# LedBlinker.net
KiCad netlist of a schematic drawn in Altium Designer
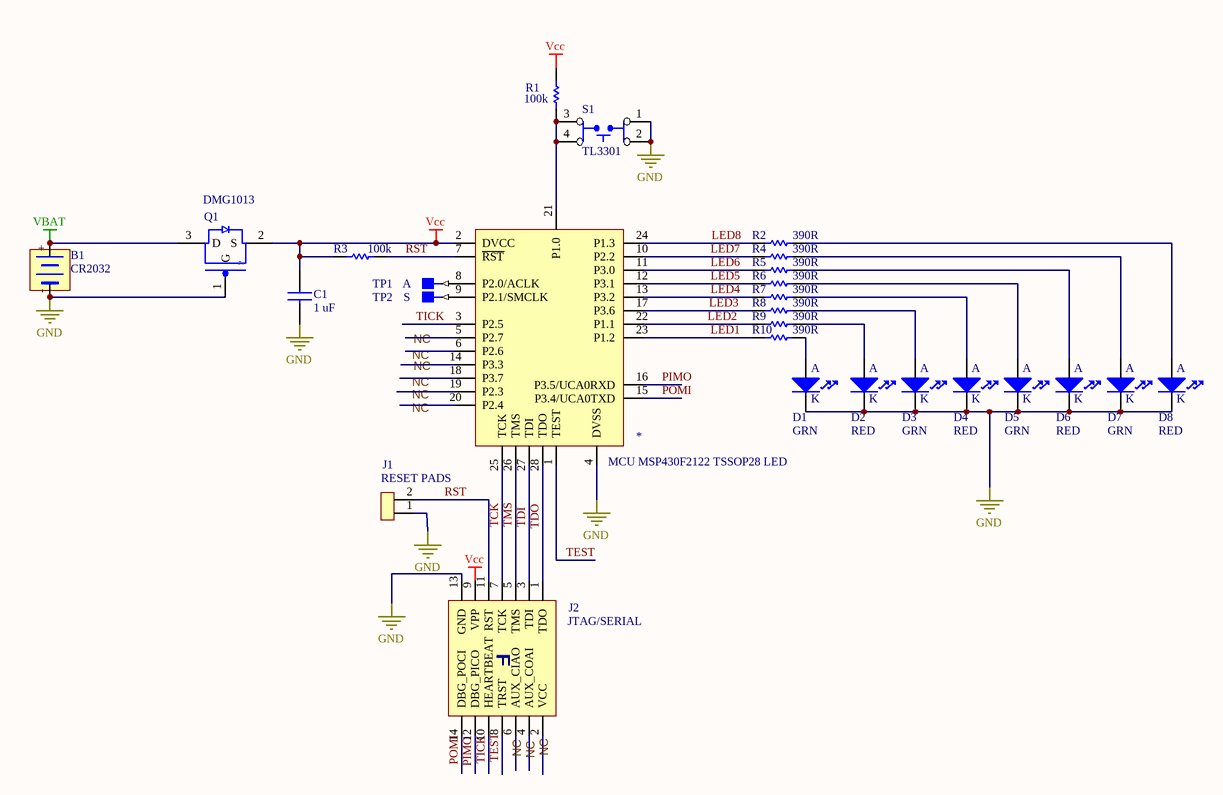
[diagram p0: LedBlinker.SchDoc]

(export (version "E")
  (design (tool "Eeschema 10.0.6"))
  (components
    (comp (ref "*")
      (value "MCU MSP430F2122 TSSOP28 LED")
      (fields (field (name "7. MODIFIED BY") "*"))
      (libsource (lib "Altium Example Master Schematic Library") (part "MCU MSP430F2122 TSSOP28 LED"))
    )
    (comp (ref "B1")
      (value "CR2032")
      (footprint "CONN BATTERY HOLDER CR2032")
      (description "3V Coincell Battery")
      (fields
        (field (name "3. MANUFACTURER PART NUMBER") "BK-912")
        (field (name "4. DIGI-KEY PART NUMBER") "BK-912-ND")
        (field (name "7. MODIFIED BY") "JRL")
      )
      (libsource (lib "Altium Example Master Schematic Library") (part "CONN BATTERY HOLDER CR2032"))
    )
    (comp (ref "C1")
      (value "1 uF")
      (footprint "0603")
      (fields (field (name "7. MODIFIED BY") "*"))
      (libsource (lib "Altium Example Master Schematic Library") (part "CAPACITOR NON-POLARIZED"))
    )
    (comp (ref "D1")
      (value "GRN")
      (footprint "PLCC-2 AK")
      (fields (field (name "7. MODIFIED BY") "*"))
      (libsource (lib "Altium Example Master Schematic Library") (part "LED AK"))
    )
    (comp (ref "D2")
      (value "RED")
      (footprint "PLCC-2 AK")
      (fields (field (name "7. MODIFIED BY") "*"))
      (libsource (lib "Altium Example Master Schematic Library") (part "LED AK"))
    )
    (comp (ref "D3")
      (value "GRN")
      (footprint "PLCC-2 AK")
      (fields (field (name "7. MODIFIED BY") "*"))
      (libsource (lib "Altium Example Master Schematic Library") (part "LED AK"))
    )
    (comp (ref "D4")
      (value "RED")
      (footprint "PLCC-2 AK")
      (fields (field (name "7. MODIFIED BY") "*"))
      (libsource (lib "Altium Example Master Schematic Library") (part "LED AK"))
    )
    (comp (ref "D5")
      (value "GRN")
      (footprint "PLCC-2 AK")
      (fields (field (name "7. MODIFIED BY") "*"))
      (libsource (lib "Altium Example Master Schematic Library") (part "LED AK"))
    )
    (comp (ref "D6")
      (value "RED")
      (footprint "PLCC-2 AK")
      (fields (field (name "7. MODIFIED BY") "*"))
      (libsource (lib "Altium Example Master Schematic Library") (part "LED AK"))
    )
    (comp (ref "D7")
      (value "GRN")
      (footprint "PLCC-2 AK")
      (fields (field (name "7. MODIFIED BY") "*"))
      (libsource (lib "Altium Example Master Schematic Library") (part "LED AK"))
    )
    (comp (ref "D8")
      (value "RED")
      (footprint "PLCC-2 AK")
      (fields (field (name "7. MODIFIED BY") "*"))
      (libsource (lib "Altium Example Master Schematic Library") (part "LED AK"))
    )
    (comp (ref "J1")
      (value "RESET PADS")
      (footprint "HDR1X2")
      (fields (field (name "7. MODIFIED BY") "*"))
      (libsource (lib "Altium Example Master Schematic Library") (part "CONN SIP 2"))
    )
    (comp (ref "J2")
      (value "JTAG/SERIAL")
      (footprint "CONN 14POS 7X2 SMT FEMALE SMALL")
      (fields
        (field (name "3. MANUFACTURER PART NUMBER") "20021321-00014T4LF")
        (field (name "4. DIGI-KEY PART NUMBER") "609-3771-ND")
        (field (name "5. INTERNAL PART NUMBER") "100254")
        (field (name "7. MODIFIED BY") "AAL")
      )
      (libsource (lib "Altium Example Master Schematic Library") (part "CONN JTAG/SERIAL FEMALE"))
    )
    (comp (ref "Q1")
      (value "DMG1013")
      (footprint "SC-70-3")
      (fields (field (name "7. MODIFIED BY") "*"))
      (libsource (lib "Altium Example Master Schematic Library") (part "TRANS PMOS 1G 2S 3D"))
    )
    (comp (ref "R1")
      (value "100k")
      (footprint "0603")
      (fields (field (name "7. MODIFIED BY") "*"))
      (libsource (lib "Altium Example Master Schematic Library") (part "RESISTOR"))
    )
    (comp (ref "R2")
      (value "390R")
      (footprint "0603")
      (fields (field (name "7. MODIFIED BY") "*"))
      (libsource (lib "Altium Example Master Schematic Library") (part "RESISTOR"))
    )
    (comp (ref "R3")
      (value "100k")
      (footprint "0603")
      (fields (field (name "7. MODIFIED BY") "*"))
      (libsource (lib "Altium Example Master Schematic Library") (part "RESISTOR"))
    )
    (comp (ref "R4")
      (value "390R")
      (footprint "0603")
      (fields (field (name "7. MODIFIED BY") "*"))
      (libsource (lib "Altium Example Master Schematic Library") (part "RESISTOR"))
    )
    (comp (ref "R5")
      (value "390R")
      (footprint "0603")
      (fields (field (name "7. MODIFIED BY") "*"))
      (libsource (lib "Altium Example Master Schematic Library") (part "RESISTOR"))
    )
    (comp (ref "R6")
      (value "390R")
      (footprint "0603")
      (fields (field (name "7. MODIFIED BY") "*"))
      (libsource (lib "Altium Example Master Schematic Library") (part "RESISTOR"))
    )
    (comp (ref "R7")
      (value "390R")
      (footprint "0603")
      (fields (field (name "7. MODIFIED BY") "*"))
      (libsource (lib "Altium Example Master Schematic Library") (part "RESISTOR"))
    )
    (comp (ref "R8")
      (value "390R")
      (footprint "0603")
      (fields (field (name "7. MODIFIED BY") "*"))
      (libsource (lib "Altium Example Master Schematic Library") (part "RESISTOR"))
    )
    (comp (ref "R9")
      (value "390R")
      (footprint "0603")
      (fields (field (name "7. MODIFIED BY") "*"))
      (libsource (lib "Altium Example Master Schematic Library") (part "RESISTOR"))
    )
    (comp (ref "R10")
      (value "390R")
      (footprint "0603")
      (fields (field (name "7. MODIFIED BY") "*"))
      (libsource (lib "Altium Example Master Schematic Library") (part "RESISTOR"))
    )
    (comp (ref "S1")
      (value "TL3301")
      (footprint "SWITCH TACT SMT TL3301 J LEAD")
      (description "SPST TACT SWITCH")
      (fields (field (name "3. MANUFACTURER PART NUMBER") "TL3301xxx") (field (name "7. MODIFIED BY") "JRL"))
      (libsource (lib "Altium Example Master Schematic Library") (part "SWITCH SPST TL3301 JLEAD"))
    )
    (comp (ref "TP1")
      (value "A")
      (footprint "TEST POINT SMT")
      (fields (field (name "7. MODIFIED BY") "JRL"))
      (libsource (lib "Altium Example Master Schematic Library") (part "TEST POINT SMT"))
    )
    (comp (ref "TP2")
      (value "S")
      (footprint "TEST POINT SMT")
      (fields (field (name "7. MODIFIED BY") "JRL"))
      (libsource (lib "Altium Example Master Schematic Library") (part "TEST POINT SMT"))
    )
  )
  (nets
    (net (code "1") (name "/LED1") (class "Default")
      (node (ref "*") (pin "23") (pinfunction "P1.2_23") (pintype "passive"))
      (node (ref "R10") (pin "1") (pinfunction "1_1") (pintype "passive"))
    )
    (net (code "2") (name "/LED2") (class "Default")
      (node (ref "*") (pin "22") (pinfunction "P1.1_22") (pintype "passive"))
      (node (ref "R9") (pin "1") (pinfunction "1_1") (pintype "passive"))
    )
    (net (code "3") (name "/LED3") (class "Default")
      (node (ref "*") (pin "17") (pinfunction "P3.6_17") (pintype "passive"))
      (node (ref "R8") (pin "1") (pinfunction "1_1") (pintype "passive"))
    )
    (net (code "4") (name "/LED4") (class "Default")
      (node (ref "*") (pin "13") (pinfunction "P3.2_13") (pintype "passive"))
      (node (ref "R7") (pin "1") (pinfunction "1_1") (pintype "passive"))
    )
    (net (code "5") (name "/LED5") (class "Default")
      (node (ref "*") (pin "12") (pinfunction "P3.1_12") (pintype "passive"))
      (node (ref "R6") (pin "1") (pinfunction "1_1") (pintype "passive"))
    )
    (net (code "6") (name "/LED6") (class "Default")
      (node (ref "*") (pin "11") (pinfunction "P3.0_11") (pintype "passive"))
      (node (ref "R5") (pin "1") (pinfunction "1_1") (pintype "passive"))
    )
    (net (code "7") (name "/LED7") (class "Default")
      (node (ref "*") (pin "10") (pinfunction "P2.2_10") (pintype "passive"))
      (node (ref "R4") (pin "1") (pinfunction "1_1") (pintype "passive"))
    )
    (net (code "8") (name "/LED8") (class "Default")
      (node (ref "*") (pin "24") (pinfunction "P1.3_24") (pintype "passive"))
      (node (ref "R2") (pin "1") (pinfunction "1_1") (pintype "passive"))
    )
    (net (code "9") (name "/PIMO") (class "Default")
      (node (ref "*") (pin "16") (pinfunction "P3.5/UCA0RXD_16") (pintype "passive"))
      (node (ref "J2") (pin "12") (pinfunction "DBG_PICO_12") (pintype "passive"))
    )
    (net (code "10") (name "/POMI") (class "Default")
      (node (ref "*") (pin "15") (pinfunction "P3.4/UCA0TXD_15") (pintype "passive"))
      (node (ref "J2") (pin "14") (pinfunction "DBG_POCI_14") (pintype "passive"))
    )
    (net (code "11") (name "/RST") (class "Default")
      (node (ref "*") (pin "7") (pinfunction "~{RST}_7") (pintype "passive"))
      (node (ref "J1") (pin "2") (pintype "passive"))
      (node (ref "J2") (pin "11") (pinfunction "RST_11") (pintype "passive"))
      (node (ref "R3") (pin "2") (pinfunction "2_2") (pintype "passive"))
    )
    (net (code "12") (name "/TCK") (class "Default")
      (node (ref "*") (pin "25") (pinfunction "TCK_25") (pintype "passive"))
      (node (ref "J2") (pin "7") (pinfunction "TCK_7") (pintype "passive"))
    )
    (net (code "13") (name "/TDI") (class "Default")
      (node (ref "*") (pin "27") (pinfunction "TDI_27") (pintype "passive"))
      (node (ref "J2") (pin "3") (pinfunction "TDI_3") (pintype "passive"))
    )
    (net (code "14") (name "/TDO") (class "Default")
      (node (ref "*") (pin "28") (pinfunction "TDO_28") (pintype "passive"))
      (node (ref "J2") (pin "1") (pinfunction "TDO_1") (pintype "passive"))
    )
    (net (code "15") (name "/TEST") (class "Default")
      (node (ref "*") (pin "1") (pinfunction "TEST_1") (pintype "passive"))
      (node (ref "J2") (pin "8") (pinfunction "TRST_8") (pintype "passive"))
    )
    (net (code "16") (name "/TICK") (class "Default")
      (node (ref "*") (pin "3") (pinfunction "P2.5_3") (pintype "passive"))
      (node (ref "J2") (pin "10") (pinfunction "HEARTBEAT_10") (pintype "passive"))
    )
    (net (code "17") (name "/TMS") (class "Default")
      (node (ref "*") (pin "26") (pinfunction "TMS_26") (pintype "passive"))
      (node (ref "J2") (pin "5") (pinfunction "TMS_5") (pintype "passive"))
    )
    (net (code "18") (name "GND") (class "Default")
      (node (ref "*") (pin "4") (pinfunction "DVSS_4") (pintype "passive"))
      (node (ref "B1") (pin "-") (pintype "passive"))
      (node (ref "C1") (pin "2") (pinfunction "2_2") (pintype "passive"))
      (node (ref "D1") (pin "K") (pinfunction "K_K") (pintype "passive"))
      (node (ref "D2") (pin "K") (pinfunction "K_K") (pintype "passive"))
      (node (ref "D3") (pin "K") (pinfunction "K_K") (pintype "passive"))
      (node (ref "D4") (pin "K") (pinfunction "K_K") (pintype "passive"))
      (node (ref "D5") (pin "K") (pinfunction "K_K") (pintype "passive"))
      (node (ref "D6") (pin "K") (pinfunction "K_K") (pintype "passive"))
      (node (ref "D7") (pin "K") (pinfunction "K_K") (pintype "passive"))
      (node (ref "D8") (pin "K") (pinfunction "K_K") (pintype "passive"))
      (node (ref "J1") (pin "1") (pintype "passive"))
      (node (ref "J2") (pin "13") (pinfunction "GND_13") (pintype "passive"))
      (node (ref "Q1") (pin "1") (pinfunction "G_1") (pintype "passive"))
      (node (ref "S1") (pin "1") (pinfunction "X1_1") (pintype "passive"))
      (node (ref "S1") (pin "2") (pinfunction "X2_2") (pintype "passive"))
    )
    (net (code "19") (name "Net-(*-P1.0)") (class "Default")
      (node (ref "*") (pin "21") (pinfunction "P1.0_21") (pintype "passive"))
      (node (ref "R1") (pin "1") (pinfunction "1_1") (pintype "passive"))
      (node (ref "S1") (pin "3") (pinfunction "Y1_3") (pintype "passive"))
      (node (ref "S1") (pin "4") (pinfunction "Y2_4") (pintype "passive"))
    )
    (net (code "20") (name "Net-(*-P2.0{slash}ACLK)") (class "Default")
      (node (ref "*") (pin "8") (pinfunction "P2.0/ACLK_8") (pintype "passive"))
      (node (ref "TP1") (pin "1") (pinfunction "1_1") (pintype "input"))
    )
    (net (code "21") (name "Net-(*-P2.1{slash}SMCLK)") (class "Default")
      (node (ref "*") (pin "9") (pinfunction "P2.1/SMCLK_9") (pintype "passive"))
      (node (ref "TP2") (pin "1") (pinfunction "1_1") (pintype "input"))
    )
    (net (code "22") (name "Net-(D1-PadA)") (class "Default")
      (node (ref "D1") (pin "A") (pinfunction "A_A") (pintype "passive"))
      (node (ref "R10") (pin "2") (pinfunction "2_2") (pintype "passive"))
    )
    (net (code "23") (name "Net-(D2-PadA)") (class "Default")
      (node (ref "D2") (pin "A") (pinfunction "A_A") (pintype "passive"))
      (node (ref "R9") (pin "2") (pinfunction "2_2") (pintype "passive"))
    )
    (net (code "24") (name "Net-(D3-PadA)") (class "Default")
      (node (ref "D3") (pin "A") (pinfunction "A_A") (pintype "passive"))
      (node (ref "R8") (pin "2") (pinfunction "2_2") (pintype "passive"))
    )
    (net (code "25") (name "Net-(D4-PadA)") (class "Default")
      (node (ref "D4") (pin "A") (pinfunction "A_A") (pintype "passive"))
      (node (ref "R7") (pin "2") (pinfunction "2_2") (pintype "passive"))
    )
    (net (code "26") (name "Net-(D5-PadA)") (class "Default")
      (node (ref "D5") (pin "A") (pinfunction "A_A") (pintype "passive"))
      (node (ref "R6") (pin "2") (pinfunction "2_2") (pintype "passive"))
    )
    (net (code "27") (name "Net-(D6-PadA)") (class "Default")
      (node (ref "D6") (pin "A") (pinfunction "A_A") (pintype "passive"))
      (node (ref "R5") (pin "2") (pinfunction "2_2") (pintype "passive"))
    )
    (net (code "28") (name "Net-(D7-PadA)") (class "Default")
      (node (ref "D7") (pin "A") (pinfunction "A_A") (pintype "passive"))
      (node (ref "R4") (pin "2") (pinfunction "2_2") (pintype "passive"))
    )
    (net (code "29") (name "Net-(D8-PadA)") (class "Default")
      (node (ref "D8") (pin "A") (pinfunction "A_A") (pintype "passive"))
      (node (ref "R2") (pin "2") (pinfunction "2_2") (pintype "passive"))
    )
    (net (code "30") (name "VBAT") (class "Default")
      (node (ref "B1") (pin "+") (pintype "passive"))
      (node (ref "Q1") (pin "3") (pinfunction "D_3") (pintype "passive"))
    )
    (net (code "31") (name "Vcc") (class "Default")
      (node (ref "*") (pin "2") (pinfunction "DVCC_2") (pintype "passive"))
      (node (ref "C1") (pin "1") (pinfunction "1_1") (pintype "passive"))
      (node (ref "J2") (pin "9") (pinfunction "VPP_9") (pintype "passive"))
      (node (ref "Q1") (pin "2") (pinfunction "S_2") (pintype "passive"))
      (node (ref "R1") (pin "2") (pinfunction "2_2") (pintype "passive"))
      (node (ref "R3") (pin "1") (pinfunction "1_1") (pintype "passive"))
    )
    (net (code "32") (name "unconnected-(*-P2.3-Pad19)") (class "Default")
      (node (ref "*") (pin "19") (pinfunction "P2.3_19") (pintype "passive"))
    )
    (net (code "33") (name "unconnected-(*-P2.4-Pad20)") (class "Default")
      (node (ref "*") (pin "20") (pinfunction "P2.4_20") (pintype "passive"))
    )
    (net (code "34") (name "unconnected-(*-P2.6-Pad6)") (class "Default")
      (node (ref "*") (pin "6") (pinfunction "P2.6_6") (pintype "passive"))
    )
    (net (code "35") (name "unconnected-(*-P2.7-Pad5)") (class "Default")
      (node (ref "*") (pin "5") (pinfunction "P2.7_5") (pintype "passive"))
    )
    (net (code "36") (name "unconnected-(*-P3.3-Pad14)") (class "Default")
      (node (ref "*") (pin "14") (pinfunction "P3.3_14") (pintype "passive"))
    )
    (net (code "37") (name "unconnected-(*-P3.7-Pad18)") (class "Default")
      (node (ref "*") (pin "18") (pinfunction "P3.7_18") (pintype "passive"))
    )
    (net (code "38") (name "unconnected-(J2-AUX_CIAO-Pad6)") (class "Default")
      (node (ref "J2") (pin "6") (pinfunction "AUX_CIAO_6") (pintype "passive"))
    )
    (net (code "39") (name "unconnected-(J2-AUX_COAI-Pad4)") (class "Default")
      (node (ref "J2") (pin "4") (pinfunction "AUX_COAI_4") (pintype "passive"))
    )
    (net (code "40") (name "unconnected-(J2-VCC-Pad2)") (class "Default")
      (node (ref "J2") (pin "2") (pinfunction "VCC_2") (pintype "passive"))
    )
  )
)
